# Timer_Settings_Schematic.net
KiCad netlist of a schematic drawn in EAGLE
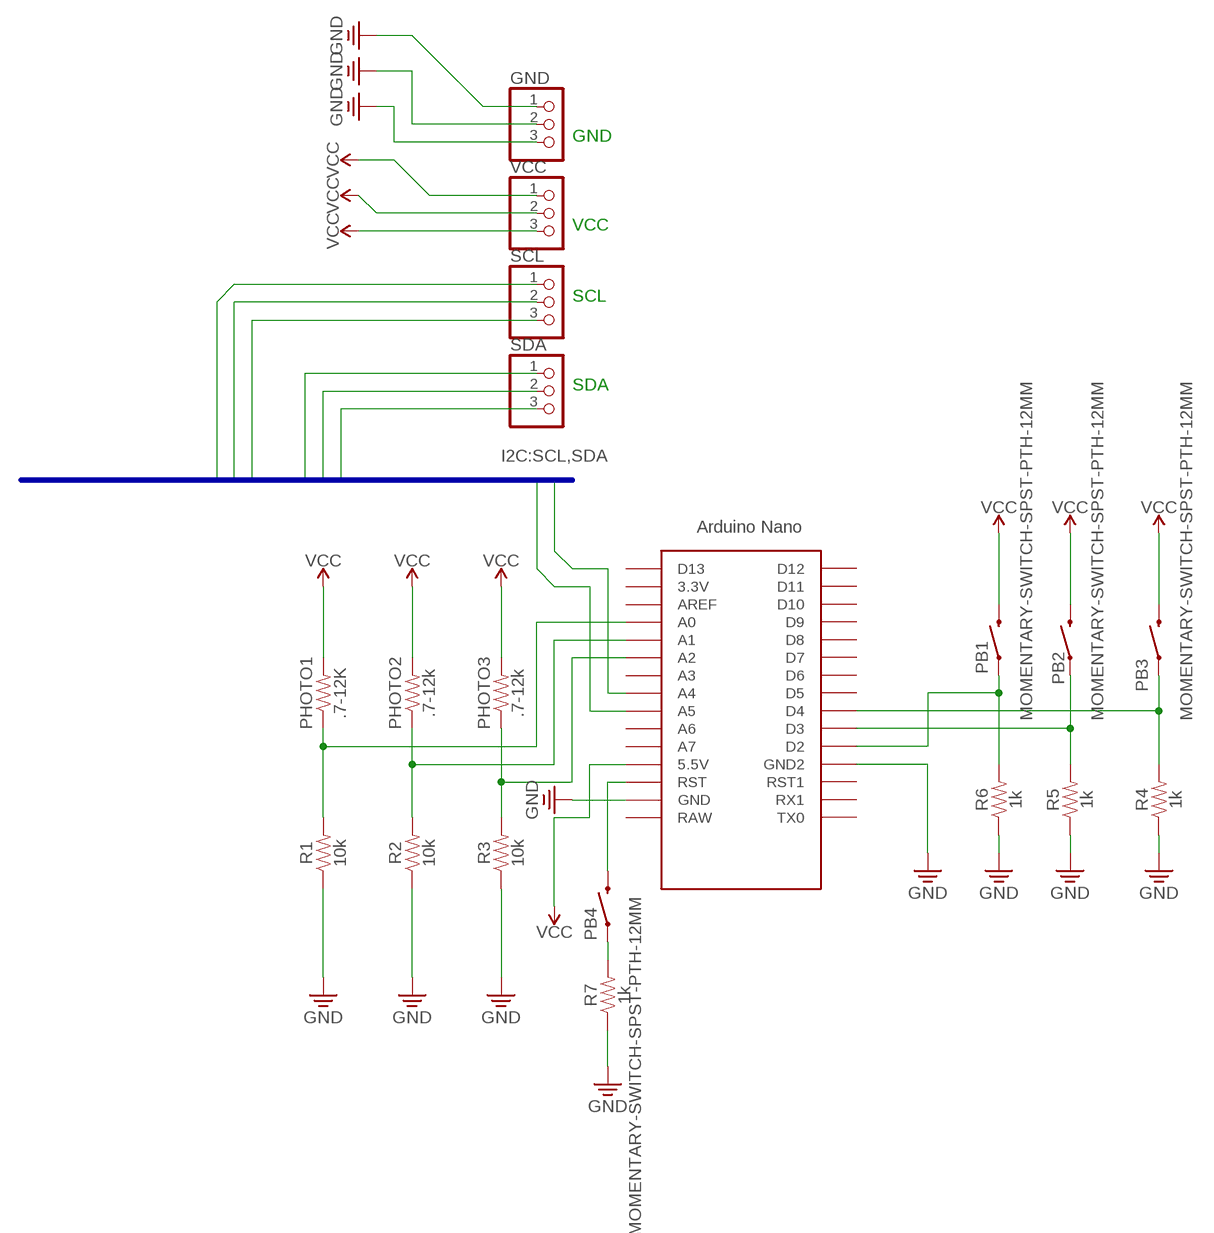
[diagram p0: schematic, sheet 1]

(export (version "E")
  (design (tool "Eeschema 10.0.6"))
  (components
    (comp (ref "GND")
      (value "PINHD-1X3CB")
      (footprint "eagle-import:1X03-CLEANBIG")
      (libsource (lib "eagle-import") (part "PINHD-1X3CB"))
    )
    (comp (ref "PB1")
      (value "MOMENTARY-SWITCH-SPST-PTH-12MM")
      (footprint "eagle-import:TACTILE_SWITCH_PTH_12MM")
      (libsource (lib "eagle-import") (part "MOMENTARY-SWITCH-SPST-PTH-12MM"))
    )
    (comp (ref "PB2")
      (value "MOMENTARY-SWITCH-SPST-PTH-12MM")
      (footprint "eagle-import:TACTILE_SWITCH_PTH_12MM")
      (libsource (lib "eagle-import") (part "MOMENTARY-SWITCH-SPST-PTH-12MM"))
    )
    (comp (ref "PB3")
      (value "MOMENTARY-SWITCH-SPST-PTH-12MM")
      (footprint "eagle-import:TACTILE_SWITCH_PTH_12MM")
      (libsource (lib "eagle-import") (part "MOMENTARY-SWITCH-SPST-PTH-12MM"))
    )
    (comp (ref "PB4")
      (value "MOMENTARY-SWITCH-SPST-PTH-12MM")
      (footprint "eagle-import:TACTILE_SWITCH_PTH_12MM")
      (libsource (lib "eagle-import") (part "MOMENTARY-SWITCH-SPST-PTH-12MM"))
    )
    (comp (ref "PHOTO1")
      (value ".7-12K")
      (footprint "eagle-import:AXIAL-0.3")
      (libsource (lib "eagle-import") (part "15KOHM-HORIZ-1/4W-5%"))
    )
    (comp (ref "PHOTO2")
      (value ".7-12k")
      (footprint "eagle-import:AXIAL-0.3")
      (libsource (lib "eagle-import") (part "15KOHM-HORIZ-1/4W-5%"))
    )
    (comp (ref "PHOTO3")
      (value ".7-12k")
      (footprint "eagle-import:AXIAL-0.3")
      (libsource (lib "eagle-import") (part "15KOHM-HORIZ-1/4W-5%"))
    )
    (comp (ref "R1")
      (value "10k")
      (footprint "eagle-import:AXIAL-0.3")
      (libsource (lib "eagle-import") (part "10KOHM-HORIZ-1/4W-1%"))
    )
    (comp (ref "R2")
      (value "10k")
      (footprint "eagle-import:AXIAL-0.3")
      (libsource (lib "eagle-import") (part "10KOHM-HORIZ-1/4W-1%"))
    )
    (comp (ref "R3")
      (value "10k")
      (footprint "eagle-import:AXIAL-0.3")
      (libsource (lib "eagle-import") (part "10KOHM-HORIZ-1/4W-1%"))
    )
    (comp (ref "R4")
      (value "1k")
      (footprint "eagle-import:AXIAL-0.3")
      (libsource (lib "eagle-import") (part "1KOHM-HORIZ-1/4W-1%"))
    )
    (comp (ref "R5")
      (value "1k")
      (footprint "eagle-import:AXIAL-0.3")
      (libsource (lib "eagle-import") (part "1KOHM-HORIZ-1/4W-1%"))
    )
    (comp (ref "R6")
      (value "1k")
      (footprint "eagle-import:AXIAL-0.3")
      (libsource (lib "eagle-import") (part "1KOHM-HORIZ-1/4W-1%"))
    )
    (comp (ref "R7")
      (value "1k")
      (footprint "eagle-import:AXIAL-0.3")
      (libsource (lib "eagle-import") (part "1KOHM-HORIZ-1/4W-1%"))
    )
    (comp (ref "SCL")
      (value "PINHD-1X3CB")
      (footprint "eagle-import:1X03-CLEANBIG")
      (libsource (lib "eagle-import") (part "PINHD-1X3CB"))
    )
    (comp (ref "SDA")
      (value "PINHD-1X3CB")
      (footprint "eagle-import:1X03-CLEANBIG")
      (libsource (lib "eagle-import") (part "PINHD-1X3CB"))
    )
    (comp (ref "U$1")
      (value "NANO")
      (footprint "eagle-import:NANO")
      (libsource (lib "eagle-import") (part "NANO"))
    )
    (comp (ref "VCC")
      (value "PINHD-1X3CB")
      (footprint "eagle-import:1X03-CLEANBIG")
      (libsource (lib "eagle-import") (part "PINHD-1X3CB"))
    )
  )
  (nets
    (net (code "2") (name "/SCL") (class "Default")
      (node (ref "SCL") (pin "1") (pinfunction "1_1") (pintype "passive"))
      (node (ref "SCL") (pin "2") (pinfunction "2_2") (pintype "passive"))
      (node (ref "SCL") (pin "3") (pinfunction "3_3") (pintype "passive"))
      (node (ref "U$1") (pin "A5") (pinfunction "A5_A5") (pintype "bidirectional"))
    )
    (net (code "3") (name "/SDA") (class "Default")
      (node (ref "SDA") (pin "1") (pinfunction "1_1") (pintype "passive"))
      (node (ref "SDA") (pin "2") (pinfunction "2_2") (pintype "passive"))
      (node (ref "SDA") (pin "3") (pinfunction "3_3") (pintype "passive"))
      (node (ref "U$1") (pin "A4") (pinfunction "A4_A4") (pintype "bidirectional"))
    )
    (net (code "5") (name "GND") (class "Default")
      (node (ref "GND") (pin "1") (pinfunction "1_1") (pintype "passive"))
      (node (ref "GND") (pin "2") (pinfunction "2_2") (pintype "passive"))
      (node (ref "GND") (pin "3") (pinfunction "3_3") (pintype "passive"))
      (node (ref "R1") (pin "P$1") (pinfunction "1_P$1") (pintype "passive"))
      (node (ref "R2") (pin "P$1") (pinfunction "1_P$1") (pintype "passive"))
      (node (ref "R3") (pin "P$1") (pinfunction "1_P$1") (pintype "passive"))
      (node (ref "R4") (pin "P$1") (pinfunction "1_P$1") (pintype "passive"))
      (node (ref "R5") (pin "P$1") (pinfunction "1_P$1") (pintype "passive"))
      (node (ref "R6") (pin "P$1") (pinfunction "1_P$1") (pintype "passive"))
      (node (ref "R7") (pin "P$1") (pinfunction "1_P$1") (pintype "passive"))
      (node (ref "U$1") (pin "GND") (pinfunction "GND_GND") (pintype "bidirectional"))
      (node (ref "U$1") (pin "GND1") (pinfunction "GND2_GND1") (pintype "bidirectional"))
    )
    (net (code "6") (name "Net-(PB4-2)") (class "Default")
      (node (ref "PB4") (pin "3") (pinfunction "2_3") (pintype "passive"))
      (node (ref "U$1") (pin "RST") (pinfunction "RST_RST") (pintype "bidirectional"))
    )
    (net (code "7") (name "Net-(PHOTO1-1)") (class "Default")
      (node (ref "PHOTO1") (pin "P$1") (pinfunction "1_P$1") (pintype "passive"))
      (node (ref "R1") (pin "P$2") (pinfunction "2_P$2") (pintype "passive"))
      (node (ref "U$1") (pin "A0") (pinfunction "A0_A0") (pintype "bidirectional"))
    )
    (net (code "8") (name "Net-(PHOTO2-1)") (class "Default")
      (node (ref "PHOTO2") (pin "P$1") (pinfunction "1_P$1") (pintype "passive"))
      (node (ref "R2") (pin "P$2") (pinfunction "2_P$2") (pintype "passive"))
      (node (ref "U$1") (pin "A1") (pinfunction "A1_A1") (pintype "bidirectional"))
    )
    (net (code "9") (name "Net-(PHOTO3-1)") (class "Default")
      (node (ref "PHOTO3") (pin "P$1") (pinfunction "1_P$1") (pintype "passive"))
      (node (ref "R3") (pin "P$2") (pinfunction "2_P$2") (pintype "passive"))
      (node (ref "U$1") (pin "A2") (pinfunction "A2_A2") (pintype "bidirectional"))
    )
    (net (code "10") (name "Net-(R4-2)") (class "Default")
      (node (ref "PB3") (pin "1") (pinfunction "1_1") (pintype "passive"))
      (node (ref "R4") (pin "P$2") (pinfunction "2_P$2") (pintype "passive"))
      (node (ref "U$1") (pin "D4") (pinfunction "D4_D4") (pintype "bidirectional"))
    )
    (net (code "11") (name "Net-(R5-2)") (class "Default")
      (node (ref "PB2") (pin "1") (pinfunction "1_1") (pintype "passive"))
      (node (ref "R5") (pin "P$2") (pinfunction "2_P$2") (pintype "passive"))
      (node (ref "U$1") (pin "D3") (pinfunction "D3_D3") (pintype "bidirectional"))
    )
    (net (code "12") (name "Net-(R6-2)") (class "Default")
      (node (ref "PB1") (pin "1") (pinfunction "1_1") (pintype "passive"))
      (node (ref "R6") (pin "P$2") (pinfunction "2_P$2") (pintype "passive"))
      (node (ref "U$1") (pin "D2") (pinfunction "D2_D2") (pintype "bidirectional"))
    )
    (net (code "13") (name "Net-(R7-2)") (class "Default")
      (node (ref "PB4") (pin "1") (pinfunction "1_1") (pintype "passive"))
      (node (ref "R7") (pin "P$2") (pinfunction "2_P$2") (pintype "passive"))
    )
    (net (code "14") (name "VCC") (class "Default")
      (node (ref "PB1") (pin "3") (pinfunction "2_3") (pintype "passive"))
      (node (ref "PB2") (pin "3") (pinfunction "2_3") (pintype "passive"))
      (node (ref "PB3") (pin "3") (pinfunction "2_3") (pintype "passive"))
      (node (ref "PHOTO1") (pin "P$2") (pinfunction "2_P$2") (pintype "passive"))
      (node (ref "PHOTO2") (pin "P$2") (pinfunction "2_P$2") (pintype "passive"))
      (node (ref "PHOTO3") (pin "P$2") (pinfunction "2_P$2") (pintype "passive"))
      (node (ref "U$1") (pin "5V") (pinfunction "5.5V_5V") (pintype "bidirectional"))
      (node (ref "VCC") (pin "1") (pinfunction "1_1") (pintype "passive"))
      (node (ref "VCC") (pin "2") (pinfunction "2_2") (pintype "passive"))
      (node (ref "VCC") (pin "3") (pinfunction "3_3") (pintype "passive"))
    )
    (net (code "15") (name "unconnected-(U$1-Pad3.3V)") (class "Default")
      (node (ref "U$1") (pin "3.3V") (pinfunction "3.3V_3.3V") (pintype "bidirectional"))
    )
    (net (code "16") (name "unconnected-(U$1-PadA3)") (class "Default")
      (node (ref "U$1") (pin "A3") (pinfunction "A3_A3") (pintype "bidirectional"))
    )
    (net (code "17") (name "unconnected-(U$1-PadA6)") (class "Default")
      (node (ref "U$1") (pin "A6") (pinfunction "A6_A6") (pintype "bidirectional"))
    )
    (net (code "18") (name "unconnected-(U$1-PadA7)") (class "Default")
      (node (ref "U$1") (pin "A7") (pinfunction "A7_A7") (pintype "bidirectional"))
    )
    (net (code "19") (name "unconnected-(U$1-PadAREF)") (class "Default")
      (node (ref "U$1") (pin "AREF") (pinfunction "AREF_AREF") (pintype "bidirectional"))
    )
    (net (code "20") (name "unconnected-(U$1-PadD5)") (class "Default")
      (node (ref "U$1") (pin "D5") (pinfunction "D5_D5") (pintype "bidirectional"))
    )
    (net (code "21") (name "unconnected-(U$1-PadD6)") (class "Default")
      (node (ref "U$1") (pin "D6") (pinfunction "D6_D6") (pintype "bidirectional"))
    )
    (net (code "22") (name "unconnected-(U$1-PadD7)") (class "Default")
      (node (ref "U$1") (pin "D7") (pinfunction "D7_D7") (pintype "bidirectional"))
    )
    (net (code "23") (name "unconnected-(U$1-PadD8)") (class "Default")
      (node (ref "U$1") (pin "D8") (pinfunction "D8_D8") (pintype "bidirectional"))
    )
    (net (code "24") (name "unconnected-(U$1-PadD9)") (class "Default")
      (node (ref "U$1") (pin "D9") (pinfunction "D9_D9") (pintype "bidirectional"))
    )
    (net (code "25") (name "unconnected-(U$1-PadD10)") (class "Default")
      (node (ref "U$1") (pin "D10") (pinfunction "D10_D10") (pintype "bidirectional"))
    )
    (net (code "26") (name "unconnected-(U$1-PadD11)") (class "Default")
      (node (ref "U$1") (pin "D11") (pinfunction "D11_D11") (pintype "bidirectional"))
    )
    (net (code "27") (name "unconnected-(U$1-PadD12)") (class "Default")
      (node (ref "U$1") (pin "D12") (pinfunction "D12_D12") (pintype "bidirectional"))
    )
    (net (code "28") (name "unconnected-(U$1-PadD13)") (class "Default")
      (node (ref "U$1") (pin "D13") (pinfunction "D13_D13") (pintype "bidirectional"))
    )
    (net (code "29") (name "unconnected-(U$1-PadICSP1)") (class "Default")
      (node (ref "U$1") (pin "ICSP1") (pinfunction "ICSP1_ICSP1") (pintype "bidirectional"))
    )
    (net (code "30") (name "unconnected-(U$1-PadICSP2)") (class "Default")
      (node (ref "U$1") (pin "ICSP2") (pinfunction "ICSP2_ICSP2") (pintype "bidirectional"))
    )
    (net (code "31") (name "unconnected-(U$1-PadICSP3)") (class "Default")
      (node (ref "U$1") (pin "ICSP3") (pinfunction "ICSP3_ICSP3") (pintype "bidirectional"))
    )
    (net (code "32") (name "unconnected-(U$1-PadICSP4)") (class "Default")
      (node (ref "U$1") (pin "ICSP4") (pinfunction "ICSP4_ICSP4") (pintype "bidirectional"))
    )
    (net (code "33") (name "unconnected-(U$1-PadICSP5)") (class "Default")
      (node (ref "U$1") (pin "ICSP5") (pinfunction "ICSP5_ICSP5") (pintype "bidirectional"))
    )
    (net (code "34") (name "unconnected-(U$1-PadICSP6)") (class "Default")
      (node (ref "U$1") (pin "ICSP6") (pinfunction "ICSP6_ICSP6") (pintype "bidirectional"))
    )
    (net (code "35") (name "unconnected-(U$1-PadRAW)") (class "Default")
      (node (ref "U$1") (pin "RAW") (pinfunction "RAW_RAW") (pintype "bidirectional"))
    )
    (net (code "36") (name "unconnected-(U$1-PadRST1)") (class "Default")
      (node (ref "U$1") (pin "RST1") (pinfunction "RST1_RST1") (pintype "bidirectional"))
    )
    (net (code "37") (name "unconnected-(U$1-PadRX1)") (class "Default")
      (node (ref "U$1") (pin "RX1") (pinfunction "RX1_RX1") (pintype "bidirectional"))
    )
    (net (code "38") (name "unconnected-(U$1-PadTX0)") (class "Default")
      (node (ref "U$1") (pin "TX0") (pinfunction "TX0_TX0") (pintype "bidirectional"))
    )
  )
)
